# pasta_razer_panthera_ps3_ps4.net
KiCad netlist of a schematic drawn in Altium Designer
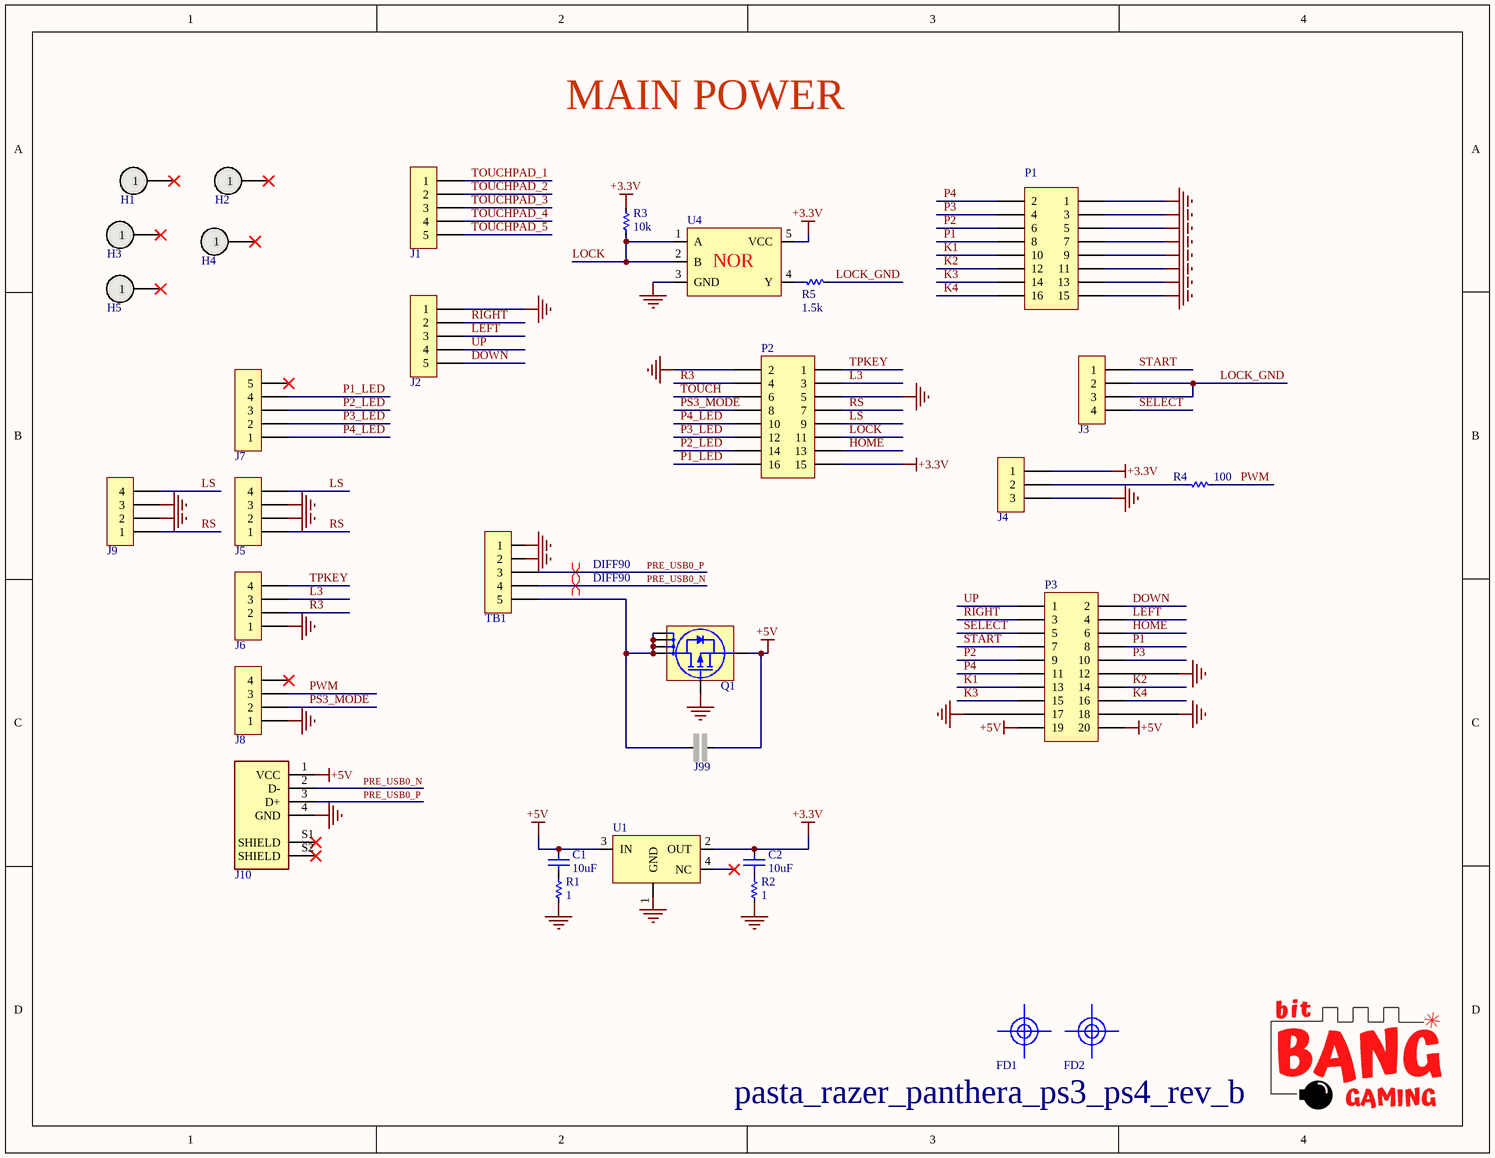
[diagram p0: pasta_razer_panthera_ps3_ps4.SchDoc]

(export (version "E")
  (design (tool "Eeschema 10.0.6"))
  (components
    (comp (ref "C1")
      (value "10uF")
      (footprint "JoesFootprintsRev2.0:C1206")
      (description "CAP CER 10UF 25V X7R 1206")
      (fields
        (field (name "MANUFACTURER PART NUMBER") "CL31B106KAHNFNE")
        (field (name "MANUFACTURER") "Samsung Electro-Mechanics")
      )
      (libsource (lib "JoesLibraryRev2.0") (part "CL31B106KAHNFNE"))
    )
    (comp (ref "C2")
      (value "10uF")
      (footprint "JoesFootprintsRev2.0:C1206")
      (description "CAP CER 10UF 25V X7R 1206")
      (fields
        (field (name "MANUFACTURER PART NUMBER") "CL31B106KAHNFNE")
        (field (name "MANUFACTURER") "Samsung Electro-Mechanics")
      )
      (libsource (lib "JoesLibraryRev2.0") (part "CL31B106KAHNFNE"))
    )
    (comp (ref "FD1")
      (value "FIDUCIAL 60MIL CIRCLE")
      (footprint "JoesFootprintsRev2.0:FIDUCIAL-SQUARE-0.060")
      (libsource (lib "JoesLibraryRev2.0") (part "FIDUCIAL 60MIL CIRCLE"))
    )
    (comp (ref "FD2")
      (value "FIDUCIAL 60MIL CIRCLE")
      (footprint "JoesFootprintsRev2.0:FIDUCIAL-SQUARE-0.060")
      (libsource (lib "JoesLibraryRev2.0") (part "FIDUCIAL 60MIL CIRCLE"))
    )
    (comp (ref "H1")
      (value "M3")
      (footprint "STANDOFF-KEYSTONE-24882")
      (description "ROUND STANDOFF M3 STEEL 3MM\"")
      (fields
        (field (name "MANUFACTURER PART NUMBER") "24882")
        (field (name "MANUFACTURER") "Keystone Electronics")
      )
      (libsource (lib "JoesLibraryRev2.0") (part "24882"))
    )
    (comp (ref "H2")
      (value "M3")
      (footprint "STANDOFF-KEYSTONE-24882")
      (description "ROUND STANDOFF M3 STEEL 3MM\"")
      (fields
        (field (name "MANUFACTURER PART NUMBER") "24882")
        (field (name "MANUFACTURER") "Keystone Electronics")
      )
      (libsource (lib "JoesLibraryRev2.0") (part "24882"))
    )
    (comp (ref "H3")
      (value "M3")
      (footprint "STANDOFF-KEYSTONE-24882")
      (description "ROUND STANDOFF M3 STEEL 3MM\"")
      (fields
        (field (name "MANUFACTURER PART NUMBER") "24882")
        (field (name "MANUFACTURER") "Keystone Electronics")
      )
      (libsource (lib "JoesLibraryRev2.0") (part "24882"))
    )
    (comp (ref "H4")
      (value "M3")
      (footprint "STANDOFF-KEYSTONE-24882")
      (description "ROUND STANDOFF M3 STEEL 3MM\"")
      (fields
        (field (name "MANUFACTURER PART NUMBER") "24882")
        (field (name "MANUFACTURER") "Keystone Electronics")
      )
      (libsource (lib "JoesLibraryRev2.0") (part "24882"))
    )
    (comp (ref "H5")
      (value "M3")
      (footprint "STANDOFF-KEYSTONE-24882")
      (description "ROUND STANDOFF M3 STEEL 3MM\"")
      (fields
        (field (name "MANUFACTURER PART NUMBER") "24882")
        (field (name "MANUFACTURER") "Keystone Electronics")
      )
      (libsource (lib "JoesLibraryRev2.0") (part "24882"))
    )
    (comp (ref "J1")
      (value "B5B-XH-A(LF)(SN)")
      (footprint "JoesFootprintsRev2.0:CONN-JST-B5B-XH-A(LF)(SN)")
      (description "CONN HEADER VERT 5POS 2.5MM")
      (fields (field (name "MANUFACTURER") "JST Sales America Inc."))
      (libsource (lib "JoesLibraryRev2.0") (part "B5B-XH-A(LF)(SN)"))
    )
    (comp (ref "J2")
      (value "B5B-XH-A(LF)(SN)")
      (footprint "JoesFootprintsRev2.0:CONN-JST-B5B-XH-A(LF)(SN)")
      (description "CONN HEADER VERT 5POS 2.5MM")
      (fields (field (name "MANUFACTURER") "JST Sales America Inc."))
      (libsource (lib "JoesLibraryRev2.0") (part "B5B-XH-A(LF)(SN)"))
    )
    (comp (ref "J3")
      (value "B4B-XH-A(LF)(SN)")
      (footprint "JoesFootprintsRev2.0:CONN-JST-B4B-XH-A(LF)(SN)")
      (description "CONN HEADER VERT 4POS 2.5MM")
      (fields (field (name "MANUFACTURER") "JST Sales America Inc."))
      (libsource (lib "JoesLibraryRev2.0") (part "B4B-XH-A(LF)(SN)"))
    )
    (comp (ref "J4")
      (value "B3B-XH-A(LF)(SN)")
      (footprint "CONN-JST-B3B-XH-A(LF)(SN)")
      (description "CONN HEADER VERT 3POS 2.5MM")
      (fields (field (name "MANUFACTURER") "JST Sales America Inc."))
      (libsource (lib "JoesLibraryRev2.0") (part "B3B-XH-A(LF)(SN)"))
    )
    (comp (ref "J5")
      (value "S4B-PH-K-S(LF)(SN)")
      (footprint "JoesFootprintsRev2.0:CONN-JST-S4B-PH-K-S(LF)(SN)")
      (description "CONN HEADER R/A 4POS 2MM")
      (fields (field (name "MANUFACTURER") "JST Sales America Inc."))
      (libsource (lib "JoesLibraryRev2.0") (part "S4B-PH-K-S(LF)(SN)"))
    )
    (comp (ref "J6")
      (value "S4B-PH-K-S(LF)(SN)")
      (footprint "JoesFootprintsRev2.0:CONN-JST-S4B-PH-K-S(LF)(SN)")
      (description "CONN HEADER R/A 4POS 2MM")
      (fields (field (name "MANUFACTURER") "JST Sales America Inc."))
      (libsource (lib "JoesLibraryRev2.0") (part "S4B-PH-K-S(LF)(SN)"))
    )
    (comp (ref "J7")
      (value "S5B-PH-K-S(LF)(SN)")
      (footprint "JoesFootprintsRev2.0:CONN-JST-S5B-PH-K-S(LF)(SN)")
      (description "CONN HEADER R/A 5POS 2MM")
      (fields (field (name "MANUFACTURER") "JST Sales America Inc."))
      (libsource (lib "JoesLibraryRev2.0") (part "S5B-PH-K-S(LF)(SN)"))
    )
    (comp (ref "J8")
      (value "S4B-PH-K-S(LF)(SN)")
      (footprint "JoesFootprintsRev2.0:CONN-JST-S4B-PH-K-S(LF)(SN)")
      (description "CONN HEADER R/A 4POS 2MM")
      (fields (field (name "MANUFACTURER") "JST Sales America Inc."))
      (libsource (lib "JoesLibraryRev2.0") (part "S4B-PH-K-S(LF)(SN)"))
    )
    (comp (ref "J9")
      (value "M20-9990446")
      (footprint "CONN-1X4-HEADER-0.100-SIL")
      (description "CONN HEADER VERT 4POS 2.54MM")
      (fields (field (name "MANUFACTURER") "Harwin Inc."))
      (libsource (lib "JoesLibraryRev2.0") (part "M20-9990446"))
    )
    (comp (ref "J10")
      (value "USB-A-S-S-W-TH")
      (footprint "JoesFootprintsRev2.0:CONN-USB-TYPE-A-FEMALE-RA")
      (description "CONN RCPT USB2.0 TYPEA 4POS R/A")
      (fields (field (name "MANUFACTURER") "Samtec"))
      (libsource (lib "JoesLibraryRev2.0") (part "USB-A-S-S-W-TH"))
    )
    (comp (ref "J99")
      (value "60 MIL SOLDER SHORT BRDIGE")
      (footprint "SOLDER-SHORT")
      (libsource (lib "JoesLibraryRev2.0") (part "SOLDER BRIDGE"))
    )
    (comp (ref "P1")
      (value "PH2-16-UA")
      (footprint "JoesFootprintsRev2.0:CONN-THRU-2X8-HEADER-0.100")
      (description "CONN HEADER VERT 16POS 2.54MM")
      (libsource (lib "JoesLibraryRev2.0") (part "PH2-16-UA"))
    )
    (comp (ref "P2")
      (value "PH2-16-UA")
      (footprint "JoesFootprintsRev2.0:CONN-THRU-2X8-HEADER-0.100")
      (description "CONN HEADER VERT 16POS 2.54MM")
      (libsource (lib "JoesLibraryRev2.0") (part "PH2-16-UA"))
    )
    (comp (ref "P3")
      (value "PH2-20-UA")
      (footprint "JoesFootprintsRev2.0:CONN-THRU-2X10-HEADER-0.100")
      (description "CONN HEADER VERT 20POS 2.54MM")
      (fields (field (name "MANUFACTURER") "Adam Tech"))
      (libsource (lib "JoesLibraryRev2.0") (part "PH2-20-UA"))
    )
    (comp (ref "Q1")
      (value "DMP3056LDM-7")
      (footprint "IC-SOT23-6")
      (description "MOSFET P-CH 30V 4.3A SOT-26")
      (fields (field (name "MANUFACTURER") "Diodes Incorporated"))
      (libsource (lib "JoesLibraryRev2.0") (part "DMP3056LDM-7"))
    )
    (comp (ref "R1")
      (value "1")
      (footprint "JoesFootprintsRev2.0:r0603")
      (description "RES SMD 1 OHM 1% 1/10W 0603")
      (fields
        (field (name "MANUFACTURER") "Vishay Dale")
        (field (name "MANUFACTURER PART NUMBER") "CRCW06031R00FKEA")
      )
      (libsource (lib "JoesLibraryRev2.0") (part "CRCW06031R00FKEA"))
    )
    (comp (ref "R2")
      (value "1")
      (footprint "JoesFootprintsRev2.0:r0603")
      (description "RES SMD 1 OHM 1% 1/10W 0603")
      (fields
        (field (name "MANUFACTURER") "Vishay Dale")
        (field (name "MANUFACTURER PART NUMBER") "CRCW06031R00FKEA")
      )
      (libsource (lib "JoesLibraryRev2.0") (part "CRCW06031R00FKEA"))
    )
    (comp (ref "R3")
      (value "10k")
      (footprint "JoesFootprintsRev2.0:r0603")
      (description "RES SMD 10K OHM 1% 1/10W 0603")
      (fields
        (field (name "MANUFACTURER") "Vishay Dale")
        (field (name "MANUFACTURER PART NUMBER") "CRCW060310K0FKEA")
      )
      (libsource (lib "JoesLibraryRev2.0") (part "CRCW060310K0FKEA"))
    )
    (comp (ref "R4")
      (value "100")
      (footprint "r0603")
      (description "RES SMD 100 OHM 1% 1/10W 0603")
      (fields
        (field (name "MANUFACTURER") "Vishay Dale")
        (field (name "MANUFACTURER PART NUMBER") "CRCW0603100RFKEA")
      )
      (libsource (lib "JoesLibraryRev2.0") (part "CRCW0603100RFKEA"))
    )
    (comp (ref "R5")
      (value "1.5k")
      (footprint "JoesFootprintsRev2.0:r0603")
      (description "RES SMD 1.5K OHM 1% 1/10W 0603")
      (fields
        (field (name "MANUFACTURER") "Vishay Dale")
        (field (name "MANUFACTURER PART NUMBER") "CRCW06031K50FKEB")
      )
      (libsource (lib "JoesLibraryRev2.0") (part "CRCW06031K50FKEB"))
    )
    (comp (ref "TB1")
      (value "OSTVN05A150")
      (footprint "TB-5PIN-OST-OSTVN05A150")
      (description "TERM BLK 5P SIDE ENT 2.54MM PCB")
      (fields (field (name "MANUFACTURER") "On Shore Technology Inc."))
      (libsource (lib "JoesLibraryRev2.0") (part "OSTVN05A150"))
    )
    (comp (ref "U1")
      (value "NCP1117LPST33T3G")
      (footprint "IC-SOT-223")
      (description "IC REG LINEAR 3.3V 1A SOT223")
      (fields (field (name "MANUFACTURER") "onsemi"))
      (libsource (lib "JoesLibraryRev2.0") (part "NCP1117LPST33T3G"))
    )
    (comp (ref "U4")
      (value "SN74AHC1G02DBVT")
      (footprint "IC-SOT23-5")
      (description "IC GATE NOR 1CH 2-INP SOT23-5")
      (fields (field (name "MANUFACTURER") "Texas Instruments"))
      (libsource (lib "JoesLibraryRev2.0") (part "SN74AHC1G02DBVT"))
    )
  )
  (nets
    (net (code "1") (name "+3.3V") (class "Default")
      (node (ref "C2") (pin "2") (pinfunction "2_2") (pintype "passive"))
      (node (ref "J4") (pin "1") (pinfunction "1_1") (pintype "passive"))
      (node (ref "P2") (pin "15") (pinfunction "15_15") (pintype "passive"))
      (node (ref "R3") (pin "2") (pinfunction "2_2") (pintype "passive"))
      (node (ref "U1") (pin "2") (pinfunction "OUT_2") (pintype "passive"))
      (node (ref "U4") (pin "5") (pinfunction "VCC_5") (pintype "passive"))
    )
    (net (code "2") (name "+5V") (class "Default")
      (node (ref "C1") (pin "2") (pinfunction "2_2") (pintype "passive"))
      (node (ref "J10") (pin "1") (pinfunction "VCC_1") (pintype "power_in"))
      (node (ref "J99") (pin "1") (pinfunction "1_1") (pintype "passive"))
      (node (ref "P3") (pin "19") (pinfunction "19_19") (pintype "passive"))
      (node (ref "P3") (pin "20") (pinfunction "20_20") (pintype "passive"))
      (node (ref "Q1") (pin "4") (pinfunction "S_4") (pintype "passive"))
      (node (ref "U1") (pin "3") (pinfunction "IN_3") (pintype "passive"))
    )
    (net (code "3") (name "/DOWN") (class "Default")
      (node (ref "J2") (pin "5") (pinfunction "5_5") (pintype "passive"))
      (node (ref "P3") (pin "2") (pinfunction "2_2") (pintype "passive"))
    )
    (net (code "4") (name "/HOME") (class "Default")
      (node (ref "P2") (pin "13") (pinfunction "13_13") (pintype "passive"))
      (node (ref "P3") (pin "6") (pinfunction "6_6") (pintype "passive"))
    )
    (net (code "5") (name "/K1") (class "Default")
      (node (ref "P1") (pin "10") (pinfunction "10_10") (pintype "passive"))
      (node (ref "P3") (pin "13") (pinfunction "13_13") (pintype "passive"))
    )
    (net (code "6") (name "/K2") (class "Default")
      (node (ref "P1") (pin "12") (pinfunction "12_12") (pintype "passive"))
      (node (ref "P3") (pin "14") (pinfunction "14_14") (pintype "passive"))
    )
    (net (code "7") (name "/K3") (class "Default")
      (node (ref "P1") (pin "14") (pinfunction "14_14") (pintype "passive"))
      (node (ref "P3") (pin "15") (pinfunction "15_15") (pintype "passive"))
    )
    (net (code "8") (name "/K4") (class "Default")
      (node (ref "P1") (pin "16") (pinfunction "16_16") (pintype "passive"))
      (node (ref "P3") (pin "16") (pinfunction "16_16") (pintype "passive"))
    )
    (net (code "9") (name "/L3") (class "Default")
      (node (ref "J6") (pin "3") (pinfunction "3_3") (pintype "passive"))
      (node (ref "P2") (pin "3") (pinfunction "3_3") (pintype "passive"))
    )
    (net (code "10") (name "/LEFT") (class "Default")
      (node (ref "J2") (pin "3") (pinfunction "3_3") (pintype "passive"))
      (node (ref "P3") (pin "4") (pinfunction "4_4") (pintype "passive"))
    )
    (net (code "11") (name "/LOCK") (class "Default")
      (node (ref "P2") (pin "11") (pinfunction "11_11") (pintype "passive"))
      (node (ref "R3") (pin "1") (pinfunction "1_1") (pintype "passive"))
      (node (ref "U4") (pin "1") (pinfunction "A_1") (pintype "passive"))
      (node (ref "U4") (pin "2") (pinfunction "B_2") (pintype "passive"))
    )
    (net (code "12") (name "/LOCK_GND") (class "Default")
      (node (ref "J3") (pin "2") (pinfunction "2_2") (pintype "passive"))
      (node (ref "J3") (pin "3") (pinfunction "3_3") (pintype "passive"))
      (node (ref "R5") (pin "2") (pinfunction "2_2") (pintype "passive"))
    )
    (net (code "13") (name "/LS") (class "Default")
      (node (ref "J5") (pin "4") (pinfunction "4_4") (pintype "passive"))
      (node (ref "J9") (pin "4") (pinfunction "4_4") (pintype "passive"))
      (node (ref "P2") (pin "9") (pinfunction "9_9") (pintype "passive"))
    )
    (net (code "14") (name "/P1") (class "Default")
      (node (ref "P1") (pin "8") (pinfunction "8_8") (pintype "passive"))
      (node (ref "P3") (pin "8") (pinfunction "8_8") (pintype "passive"))
    )
    (net (code "15") (name "/P1_LED") (class "Default")
      (node (ref "J7") (pin "4") (pinfunction "4_4") (pintype "passive"))
      (node (ref "P2") (pin "16") (pinfunction "16_16") (pintype "passive"))
    )
    (net (code "16") (name "/P2") (class "Default")
      (node (ref "P1") (pin "6") (pinfunction "6_6") (pintype "passive"))
      (node (ref "P3") (pin "9") (pinfunction "9_9") (pintype "passive"))
    )
    (net (code "17") (name "/P2_LED") (class "Default")
      (node (ref "J7") (pin "3") (pinfunction "3_3") (pintype "passive"))
      (node (ref "P2") (pin "14") (pinfunction "14_14") (pintype "passive"))
    )
    (net (code "18") (name "/P3") (class "Default")
      (node (ref "P1") (pin "4") (pinfunction "4_4") (pintype "passive"))
      (node (ref "P3") (pin "10") (pinfunction "10_10") (pintype "passive"))
    )
    (net (code "19") (name "/P3_LED") (class "Default")
      (node (ref "J7") (pin "2") (pinfunction "2_2") (pintype "passive"))
      (node (ref "P2") (pin "12") (pinfunction "12_12") (pintype "passive"))
    )
    (net (code "20") (name "/P4") (class "Default")
      (node (ref "P1") (pin "2") (pinfunction "2_2") (pintype "passive"))
      (node (ref "P3") (pin "11") (pinfunction "11_11") (pintype "passive"))
    )
    (net (code "21") (name "/P4_LED") (class "Default")
      (node (ref "J7") (pin "1") (pinfunction "1_1") (pintype "passive"))
      (node (ref "P2") (pin "10") (pinfunction "10_10") (pintype "passive"))
    )
    (net (code "22") (name "/PRE_USB0_N") (class "Default")
      (node (ref "J10") (pin "2") (pinfunction "D-_2") (pintype "passive"))
      (node (ref "TB1") (pin "4") (pinfunction "4_4") (pintype "passive"))
    )
    (net (code "23") (name "/PRE_USB0_P") (class "Default")
      (node (ref "J10") (pin "3") (pinfunction "D+_3") (pintype "passive"))
      (node (ref "TB1") (pin "3") (pinfunction "3_3") (pintype "passive"))
    )
    (net (code "24") (name "/PS3_MODE") (class "Default")
      (node (ref "J8") (pin "2") (pinfunction "2_2") (pintype "passive"))
      (node (ref "P2") (pin "8") (pinfunction "8_8") (pintype "passive"))
    )
    (net (code "25") (name "/PWM") (class "Default")
      (node (ref "J8") (pin "3") (pinfunction "3_3") (pintype "passive"))
      (node (ref "R4") (pin "2") (pinfunction "2_2") (pintype "passive"))
    )
    (net (code "26") (name "/R3") (class "Default")
      (node (ref "J6") (pin "2") (pinfunction "2_2") (pintype "passive"))
      (node (ref "P2") (pin "4") (pinfunction "4_4") (pintype "passive"))
    )
    (net (code "27") (name "/RIGHT") (class "Default")
      (node (ref "J2") (pin "2") (pinfunction "2_2") (pintype "passive"))
      (node (ref "P3") (pin "3") (pinfunction "3_3") (pintype "passive"))
    )
    (net (code "28") (name "/RS") (class "Default")
      (node (ref "J5") (pin "1") (pinfunction "1_1") (pintype "passive"))
      (node (ref "J9") (pin "1") (pinfunction "1_1") (pintype "passive"))
      (node (ref "P2") (pin "7") (pinfunction "7_7") (pintype "passive"))
    )
    (net (code "29") (name "/SELECT") (class "Default")
      (node (ref "J3") (pin "4") (pinfunction "4_4") (pintype "passive"))
      (node (ref "P3") (pin "5") (pinfunction "5_5") (pintype "passive"))
    )
    (net (code "30") (name "/START") (class "Default")
      (node (ref "J3") (pin "1") (pinfunction "1_1") (pintype "passive"))
      (node (ref "P3") (pin "7") (pinfunction "7_7") (pintype "passive"))
    )
    (net (code "31") (name "/TOUCH") (class "Default")
      (node (ref "P2") (pin "6") (pinfunction "6_6") (pintype "passive"))
    )
    (net (code "32") (name "/TOUCHPAD_1") (class "Default")
      (node (ref "J1") (pin "1") (pinfunction "1_1") (pintype "passive"))
    )
    (net (code "33") (name "/TOUCHPAD_2") (class "Default")
      (node (ref "J1") (pin "2") (pinfunction "2_2") (pintype "passive"))
    )
    (net (code "34") (name "/TOUCHPAD_3") (class "Default")
      (node (ref "J1") (pin "3") (pinfunction "3_3") (pintype "passive"))
    )
    (net (code "35") (name "/TOUCHPAD_4") (class "Default")
      (node (ref "J1") (pin "4") (pinfunction "4_4") (pintype "passive"))
    )
    (net (code "36") (name "/TOUCHPAD_5") (class "Default")
      (node (ref "J1") (pin "5") (pinfunction "5_5") (pintype "passive"))
    )
    (net (code "37") (name "/TPKEY") (class "Default")
      (node (ref "J6") (pin "4") (pinfunction "4_4") (pintype "passive"))
      (node (ref "P2") (pin "1") (pinfunction "1_1") (pintype "passive"))
    )
    (net (code "38") (name "/UP") (class "Default")
      (node (ref "J2") (pin "4") (pinfunction "4_4") (pintype "passive"))
      (node (ref "P3") (pin "1") (pinfunction "1_1") (pintype "passive"))
    )
    (net (code "39") (name "GND") (class "Default")
      (node (ref "J10") (pin "4") (pinfunction "GND_4") (pintype "power_in"))
      (node (ref "J2") (pin "1") (pinfunction "1_1") (pintype "passive"))
      (node (ref "J4") (pin "3") (pinfunction "3_3") (pintype "passive"))
      (node (ref "J5") (pin "2") (pinfunction "2_2") (pintype "passive"))
      (node (ref "J5") (pin "3") (pinfunction "3_3") (pintype "passive"))
      (node (ref "J6") (pin "1") (pinfunction "1_1") (pintype "passive"))
      (node (ref "J8") (pin "1") (pinfunction "1_1") (pintype "passive"))
      (node (ref "J9") (pin "2") (pinfunction "2_2") (pintype "passive"))
      (node (ref "J9") (pin "3") (pinfunction "3_3") (pintype "passive"))
      (node (ref "P1") (pin "1") (pinfunction "1_1") (pintype "passive"))
      (node (ref "P1") (pin "11") (pinfunction "11_11") (pintype "passive"))
      (node (ref "P1") (pin "13") (pinfunction "13_13") (pintype "passive"))
      (node (ref "P1") (pin "15") (pinfunction "15_15") (pintype "passive"))
      (node (ref "P1") (pin "3") (pinfunction "3_3") (pintype "passive"))
      (node (ref "P1") (pin "5") (pinfunction "5_5") (pintype "passive"))
      (node (ref "P1") (pin "7") (pinfunction "7_7") (pintype "passive"))
      (node (ref "P1") (pin "9") (pinfunction "9_9") (pintype "passive"))
      (node (ref "P2") (pin "2") (pinfunction "2_2") (pintype "passive"))
      (node (ref "P2") (pin "5") (pinfunction "5_5") (pintype "passive"))
      (node (ref "P3") (pin "12") (pinfunction "12_12") (pintype "passive"))
      (node (ref "P3") (pin "17") (pinfunction "17_17") (pintype "passive"))
      (node (ref "P3") (pin "18") (pinfunction "18_18") (pintype "passive"))
      (node (ref "Q1") (pin "3") (pinfunction "G_3") (pintype "passive"))
      (node (ref "R1") (pin "2") (pinfunction "2_2") (pintype "passive"))
      (node (ref "R2") (pin "2") (pinfunction "2_2") (pintype "passive"))
      (node (ref "TB1") (pin "1") (pinfunction "1_1") (pintype "passive"))
      (node (ref "TB1") (pin "2") (pinfunction "2_2") (pintype "passive"))
      (node (ref "U1") (pin "1") (pinfunction "GND_1") (pintype "passive"))
      (node (ref "U4") (pin "3") (pinfunction "GND_3") (pintype "passive"))
    )
    (net (code "40") (name "Net-(C1-Pad1)") (class "Default")
      (node (ref "C1") (pin "1") (pinfunction "1_1") (pintype "passive"))
      (node (ref "R1") (pin "1") (pinfunction "1_1") (pintype "passive"))
    )
    (net (code "41") (name "Net-(C2-Pad1)") (class "Default")
      (node (ref "C2") (pin "1") (pinfunction "1_1") (pintype "passive"))
      (node (ref "R2") (pin "1") (pinfunction "1_1") (pintype "passive"))
    )
    (net (code "42") (name "Net-(J4-Pad2)") (class "Default")
      (node (ref "J4") (pin "2") (pinfunction "2_2") (pintype "passive"))
      (node (ref "R4") (pin "1") (pinfunction "1_1") (pintype "passive"))
    )
    (net (code "43") (name "Net-(J99-Pad2)") (class "Default")
      (node (ref "J99") (pin "2") (pinfunction "2_2") (pintype "passive"))
      (node (ref "Q1") (pin "1") (pinfunction "D_1") (pintype "passive"))
      (node (ref "Q1") (pin "2") (pinfunction "D_2") (pintype "passive"))
      (node (ref "Q1") (pin "5") (pinfunction "D_5") (pintype "passive"))
      (node (ref "Q1") (pin "6") (pinfunction "D_6") (pintype "passive"))
      (node (ref "TB1") (pin "5") (pinfunction "5_5") (pintype "passive"))
    )
    (net (code "44") (name "Net-(U4-Y)") (class "Default")
      (node (ref "R5") (pin "1") (pinfunction "1_1") (pintype "passive"))
      (node (ref "U4") (pin "4") (pinfunction "Y_4") (pintype "passive"))
    )
    (net (code "45") (name "unconnected-(H1-Pad1)") (class "Default")
      (node (ref "H1") (pin "1") (pinfunction "1_1") (pintype "passive+no_connect"))
    )
    (net (code "46") (name "unconnected-(H2-Pad1)") (class "Default")
      (node (ref "H2") (pin "1") (pinfunction "1_1") (pintype "passive+no_connect"))
    )
    (net (code "47") (name "unconnected-(H3-Pad1)") (class "Default")
      (node (ref "H3") (pin "1") (pinfunction "1_1") (pintype "passive+no_connect"))
    )
    (net (code "48") (name "unconnected-(H4-Pad1)") (class "Default")
      (node (ref "H4") (pin "1") (pinfunction "1_1") (pintype "passive+no_connect"))
    )
    (net (code "49") (name "unconnected-(H5-Pad1)") (class "Default")
      (node (ref "H5") (pin "1") (pinfunction "1_1") (pintype "passive+no_connect"))
    )
    (net (code "50") (name "unconnected-(J7-Pad5)") (class "Default")
      (node (ref "J7") (pin "5") (pinfunction "5_5") (pintype "passive+no_connect"))
    )
    (net (code "51") (name "unconnected-(J8-Pad4)") (class "Default")
      (node (ref "J8") (pin "4") (pinfunction "4_4") (pintype "passive+no_connect"))
    )
    (net (code "52") (name "unconnected-(J10-SHIELD-PadS1)") (class "Default")
      (node (ref "J10") (pin "S1") (pinfunction "SHIELD_S1") (pintype "passive+no_connect"))
    )
    (net (code "53") (name "unconnected-(J10-SHIELD-PadS2)") (class "Default")
      (node (ref "J10") (pin "S2") (pinfunction "SHIELD_S2") (pintype "passive+no_connect"))
    )
    (net (code "54") (name "unconnected-(U1-NC-Pad4)") (class "Default")
      (node (ref "U1") (pin "4") (pinfunction "NC_4") (pintype "passive+no_connect"))
    )
  )
)
